# DISCRETE_INPUT.net
KiCad netlist of a schematic drawn in Altium Designer
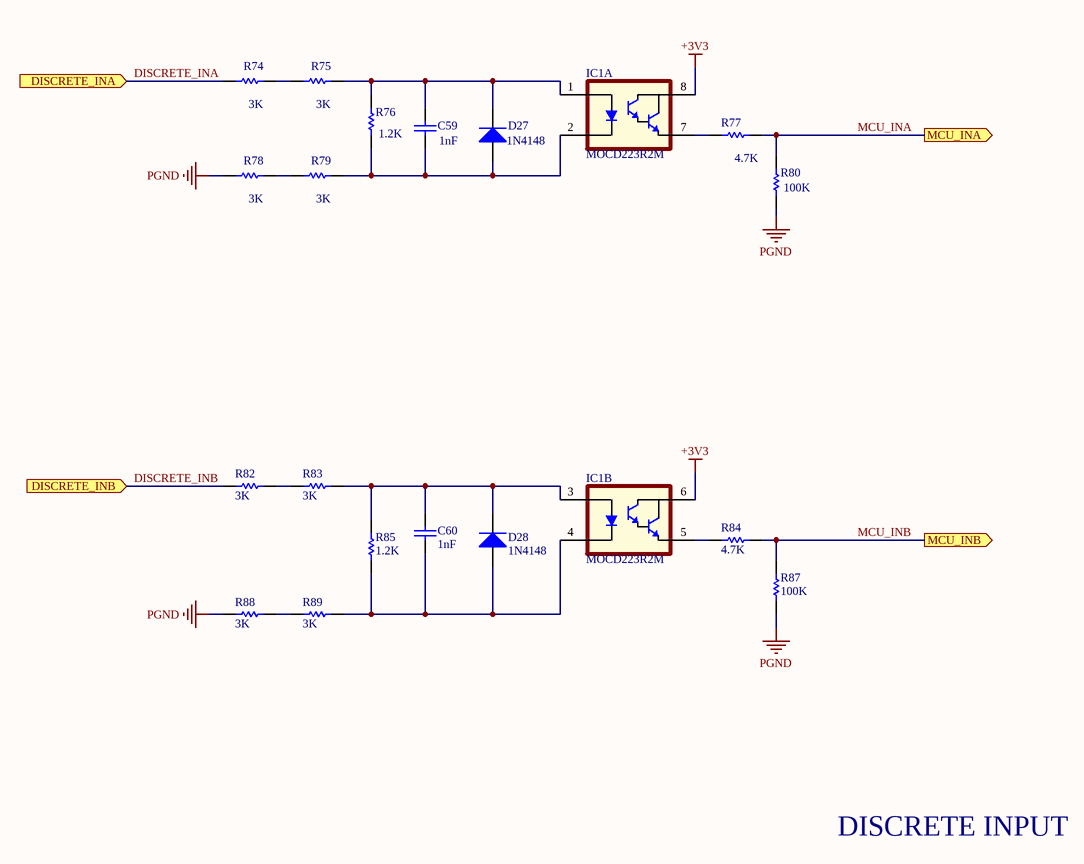
[diagram p0: DISCRETE_INPUT.SchDoc]

(export (version "E")
  (design (tool "Eeschema 10.0.6"))
  (components
    (comp (ref "C59")
      (value "1nF")
      (footprint "C 0603(1608)x0.8_3")
      (description "Cap Ceramic 0.001uF 50V X7R 10% SMD 0603 125C Paper T/R")
      (fields
        (field (name "MANUFACTURER") "Murata")
        (field (name "MANUFACTURER PART NUMBER") "GCM188R71H102KA37D")
      )
      (libsource (lib "CAPACITOR_LIB") (part "CAP CER 1NF 10% 2KV X7R SMD 1206"))
    )
    (comp (ref "C60")
      (value "1nF")
      (footprint "C 0603(1608)x0.8_3")
      (description "Cap Ceramic 0.001uF 50V X7R 10% SMD 0603 125C Paper T/R")
      (fields
        (field (name "MANUFACTURER") "Murata")
        (field (name "MANUFACTURER PART NUMBER") "GCM188R71H102KA37D")
      )
      (libsource (lib "CAPACITOR_LIB") (part "CAP CER 1NF 10% 2KV X7R SMD 1206"))
    )
    (comp (ref "D27")
      (value "1N4148")
      (footprint "SOD123")
      (description "DIODE 1N4148 GEN PURP 100V 150MA SOD123")
      (fields (field (name "MANUFACTURER") "MICRO COMMERCIAL"))
      (libsource (lib "DISCRETE_LIB") (part "DIODE 1N4148 GEN PURP 100V 150MA SOD123"))
    )
    (comp (ref "D28")
      (value "1N4148")
      (footprint "SOD123")
      (description "DIODE 1N4148 GEN PURP 100V 150MA SOD123")
      (fields (field (name "MANUFACTURER") "MICRO COMMERCIAL"))
      (libsource (lib "DISCRETE_LIB") (part "DIODE 1N4148 GEN PURP 100V 150MA SOD123"))
    )
    (comp (ref "IC1")
      (value "MOCD223R2M")
      (footprint "SOIC127P600-8N")
      (description "IC OPTOISO DARLINGTON OUTPUT MOCD223R2M 2CH VCE 30V SOIC8")
      (fields (field (name "MANUFACTURER") "FAIRCHILD"))
      (libsource (lib "IC_LIB") (part "MOCD223R2M"))
    )
    (comp (ref "R74")
      (value "3K")
      (footprint "R 0603(1608)")
      (description "RES SMD 3K OHM 1% 1/10W 0603")
      (fields
        (field (name "MANUFACTURER") "Yageo")
        (field (name "MANUFACTURER PART NUMBER") "RC0603FR-073KL")
      )
      (libsource (lib "RESISTOR_LIB") (part "RES CHIP 3K 1% 1/4W SMD 1206"))
    )
    (comp (ref "R75")
      (value "3K")
      (footprint "R 0603(1608)")
      (description "RES SMD 3K OHM 1% 1/10W 0603")
      (fields
        (field (name "MANUFACTURER") "Yageo")
        (field (name "MANUFACTURER PART NUMBER") "RC0603FR-073KL")
      )
      (libsource (lib "RESISTOR_LIB") (part "RES CHIP 3K 1% 1/4W SMD 1206"))
    )
    (comp (ref "R76")
      (value "1.2K")
      (footprint "R 0603(1608)")
      (description "RES SMD 1.2K OHM 1% 1/10W 0603")
      (fields
        (field (name "MANUFACTURER") "Vishay")
        (field (name "MANUFACTURER PART NUMBER") "CRCW06031K20FKEA")
      )
      (libsource (lib "RESISTOR_LIB") (part "RES CHIP 1K2 5% 1/4W SMD 1206"))
    )
    (comp (ref "R77")
      (value "4.7K")
      (footprint "R 0603(1608)")
      (description "RES SMD 4.7K OHM 1% 1/10W 0603")
      (fields
        (field (name "MANUFACTURER") "Yageo")
        (field (name "MANUFACTURER PART NUMBER") "RC0603FR-074K7L")
      )
      (libsource (lib "RESISTOR_LIB") (part "RES CHIP 4K7 5% 1/16W SMD 0402"))
    )
    (comp (ref "R78")
      (value "3K")
      (footprint "R 0603(1608)")
      (description "RES SMD 3K OHM 1% 1/10W 0603")
      (fields
        (field (name "MANUFACTURER") "Yageo")
        (field (name "MANUFACTURER PART NUMBER") "RC0603FR-073KL")
      )
      (libsource (lib "RESISTOR_LIB") (part "RES CHIP 3K 1% 1/4W SMD 1206"))
    )
    (comp (ref "R79")
      (value "3K")
      (footprint "R 0603(1608)")
      (description "RES SMD 3K OHM 1% 1/10W 0603")
      (fields
        (field (name "MANUFACTURER") "Yageo")
        (field (name "MANUFACTURER PART NUMBER") "RC0603FR-073KL")
      )
      (libsource (lib "RESISTOR_LIB") (part "RES CHIP 3K 1% 1/4W SMD 1206"))
    )
    (comp (ref "R80")
      (value "100K")
      (footprint "R 0603(1608)")
      (description "Res Thick Film 1.6 x 0.8 mm 100K Ohm 1% 0.1W(1/10W) 100ppm/ C Molded SMD Paper T/R")
      (fields
        (field (name "MANUFACTURER") "Yageo")
        (field (name "MANUFACTURER PART NUMBER") "RC0603FR-07100KL")
      )
      (libsource (lib "RESISTOR_LIB") (part "RES CHIP 100K 1% 1/16W SMD 0402"))
    )
    (comp (ref "R82")
      (value "3K")
      (footprint "R 0603(1608)")
      (description "RES SMD 3K OHM 1% 1/10W 0603")
      (fields
        (field (name "MANUFACTURER") "Yageo")
        (field (name "MANUFACTURER PART NUMBER") "RC0603FR-073KL")
      )
      (libsource (lib "RESISTOR_LIB") (part "RES CHIP 3K 1% 1/4W SMD 1206"))
    )
    (comp (ref "R83")
      (value "3K")
      (footprint "R 0603(1608)")
      (description "RES SMD 3K OHM 1% 1/10W 0603")
      (fields
        (field (name "MANUFACTURER") "Yageo")
        (field (name "MANUFACTURER PART NUMBER") "RC0603FR-073KL")
      )
      (libsource (lib "RESISTOR_LIB") (part "RES CHIP 3K 1% 1/4W SMD 1206"))
    )
    (comp (ref "R84")
      (value "4.7K")
      (footprint "R 0603(1608)")
      (description "RES SMD 4.7K OHM 1% 1/10W 0603")
      (fields
        (field (name "MANUFACTURER") "Yageo")
        (field (name "MANUFACTURER PART NUMBER") "RC0603FR-074K7L")
      )
      (libsource (lib "RESISTOR_LIB") (part "RES CHIP 4K7 5% 1/16W SMD 0402"))
    )
    (comp (ref "R85")
      (value "1.2K")
      (footprint "R 0603(1608)")
      (description "RES SMD 1.2K OHM 1% 1/10W 0603")
      (fields
        (field (name "MANUFACTURER") "Vishay")
        (field (name "MANUFACTURER PART NUMBER") "CRCW06031K20FKEA")
      )
      (libsource (lib "RESISTOR_LIB") (part "RES CHIP 1K2 5% 1/4W SMD 1206"))
    )
    (comp (ref "R87")
      (value "100K")
      (footprint "R 0603(1608)")
      (description "Res Thick Film 1.6 x 0.8 mm 100K Ohm 1% 0.1W(1/10W) 100ppm/ C Molded SMD Paper T/R")
      (fields
        (field (name "MANUFACTURER") "Yageo")
        (field (name "MANUFACTURER PART NUMBER") "RC0603FR-07100KL")
      )
      (libsource (lib "RESISTOR_LIB") (part "RES CHIP 100K 1% 1/16W SMD 0402"))
    )
    (comp (ref "R88")
      (value "3K")
      (footprint "R 0603(1608)")
      (description "RES SMD 3K OHM 1% 1/10W 0603")
      (fields
        (field (name "MANUFACTURER") "Yageo")
        (field (name "MANUFACTURER PART NUMBER") "RC0603FR-073KL")
      )
      (libsource (lib "RESISTOR_LIB") (part "RES CHIP 3K 1% 1/4W SMD 1206"))
    )
    (comp (ref "R89")
      (value "3K")
      (footprint "R 0603(1608)")
      (description "RES SMD 3K OHM 1% 1/10W 0603")
      (fields
        (field (name "MANUFACTURER") "Yageo")
        (field (name "MANUFACTURER PART NUMBER") "RC0603FR-073KL")
      )
      (libsource (lib "RESISTOR_LIB") (part "RES CHIP 3K 1% 1/4W SMD 1206"))
    )
  )
  (nets
    (net (code "1") (name "+3V3") (class "Default")
      (node (ref "IC1") (pin "6") (pinfunction "6_6") (pintype "passive"))
      (node (ref "IC1") (pin "8") (pinfunction "8_8") (pintype "passive"))
    )
    (net (code "2") (name "/DISCRETE_INA") (class "Default")
      (node (ref "R74") (pin "1") (pinfunction "1_1") (pintype "passive"))
    )
    (net (code "3") (name "/DISCRETE_INB") (class "Default")
      (node (ref "R82") (pin "1") (pinfunction "1_1") (pintype "passive"))
    )
    (net (code "4") (name "/MCU_INA") (class "Default")
      (node (ref "R77") (pin "2") (pinfunction "2_2") (pintype "passive"))
      (node (ref "R80") (pin "2") (pinfunction "2_2") (pintype "passive"))
    )
    (net (code "5") (name "/MCU_INB") (class "Default")
      (node (ref "R84") (pin "2") (pinfunction "2_2") (pintype "passive"))
      (node (ref "R87") (pin "2") (pinfunction "2_2") (pintype "passive"))
    )
    (net (code "6") (name "Net-(D27-A)") (class "Default")
      (node (ref "C59") (pin "1") (pinfunction "1_1") (pintype "passive"))
      (node (ref "D27") (pin "1") (pinfunction "A_1") (pintype "passive"))
      (node (ref "IC1") (pin "2") (pinfunction "2_2") (pintype "passive"))
      (node (ref "R76") (pin "1") (pinfunction "1_1") (pintype "passive"))
      (node (ref "R79") (pin "2") (pinfunction "2_2") (pintype "passive"))
    )
    (net (code "7") (name "Net-(D27-K)") (class "Default")
      (node (ref "C59") (pin "2") (pinfunction "2_2") (pintype "passive"))
      (node (ref "D27") (pin "2") (pinfunction "K_2") (pintype "passive"))
      (node (ref "IC1") (pin "1") (pinfunction "1_1") (pintype "passive"))
      (node (ref "R75") (pin "2") (pinfunction "2_2") (pintype "passive"))
      (node (ref "R76") (pin "2") (pinfunction "2_2") (pintype "passive"))
    )
    (net (code "8") (name "Net-(D28-A)") (class "Default")
      (node (ref "C60") (pin "1") (pinfunction "1_1") (pintype "passive"))
      (node (ref "D28") (pin "1") (pinfunction "A_1") (pintype "passive"))
      (node (ref "IC1") (pin "4") (pinfunction "4_4") (pintype "passive"))
      (node (ref "R85") (pin "1") (pinfunction "1_1") (pintype "passive"))
      (node (ref "R89") (pin "2") (pinfunction "2_2") (pintype "passive"))
    )
    (net (code "9") (name "Net-(D28-K)") (class "Default")
      (node (ref "C60") (pin "2") (pinfunction "2_2") (pintype "passive"))
      (node (ref "D28") (pin "2") (pinfunction "K_2") (pintype "passive"))
      (node (ref "IC1") (pin "3") (pinfunction "3_3") (pintype "passive"))
      (node (ref "R83") (pin "2") (pinfunction "2_2") (pintype "passive"))
      (node (ref "R85") (pin "2") (pinfunction "2_2") (pintype "passive"))
    )
    (net (code "10") (name "Net-(IC1-Pad5)") (class "Default")
      (node (ref "IC1") (pin "5") (pinfunction "5_5") (pintype "passive"))
      (node (ref "R84") (pin "1") (pinfunction "1_1") (pintype "passive"))
    )
    (net (code "11") (name "Net-(IC1-Pad7)") (class "Default")
      (node (ref "IC1") (pin "7") (pinfunction "7_7") (pintype "passive"))
      (node (ref "R77") (pin "1") (pinfunction "1_1") (pintype "passive"))
    )
    (net (code "12") (name "Net-(R74-Pad2)") (class "Default")
      (node (ref "R74") (pin "2") (pinfunction "2_2") (pintype "passive"))
      (node (ref "R75") (pin "1") (pinfunction "1_1") (pintype "passive"))
    )
    (net (code "13") (name "Net-(R78-Pad2)") (class "Default")
      (node (ref "R78") (pin "2") (pinfunction "2_2") (pintype "passive"))
      (node (ref "R79") (pin "1") (pinfunction "1_1") (pintype "passive"))
    )
    (net (code "14") (name "Net-(R82-Pad2)") (class "Default")
      (node (ref "R82") (pin "2") (pinfunction "2_2") (pintype "passive"))
      (node (ref "R83") (pin "1") (pinfunction "1_1") (pintype "passive"))
    )
    (net (code "15") (name "Net-(R88-Pad2)") (class "Default")
      (node (ref "R88") (pin "2") (pinfunction "2_2") (pintype "passive"))
      (node (ref "R89") (pin "1") (pinfunction "1_1") (pintype "passive"))
    )
    (net (code "16") (name "PGND") (class "Default")
      (node (ref "R78") (pin "1") (pinfunction "1_1") (pintype "passive"))
      (node (ref "R80") (pin "1") (pinfunction "1_1") (pintype "passive"))
      (node (ref "R87") (pin "1") (pinfunction "1_1") (pintype "passive"))
      (node (ref "R88") (pin "1") (pinfunction "1_1") (pintype "passive"))
    )
  )
)
